# LED_I2C_Plug-Miller.net
KiCad netlist of a schematic drawn in EAGLE
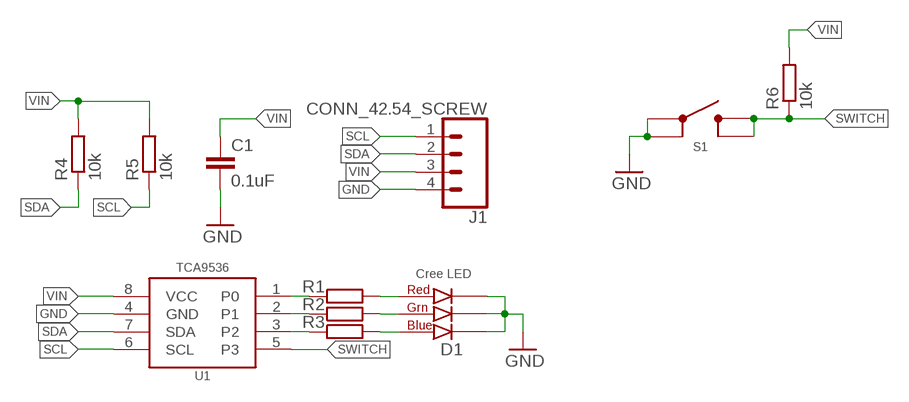
[diagram p0: schematic, sheet 1]

(export (version "E")
  (design (tool "Eeschema 10.0.6"))
  (components
    (comp (ref "C1")
      (value "0.1uF")
      (footprint "eagle-import:C0603")
      (fields (field (name "MF") "Murata") (field (name "MPN") "GCM188R71E104KA57D"))
      (libsource (lib "eagle-import") (part "C-EUC06030.1UF"))
    )
    (comp (ref "D1")
      (value "CLX6F-FKC")
      (footprint "eagle-import:CLX6F-FKC")
      (libsource (lib "eagle-import") (part "CLX6F-FKC"))
    )
    (comp (ref "J1")
      (value "CONN_42.54_SCREW")
      (footprint "eagle-import:1X04_SCREW")
      (fields (field (name "MF") "On Shore") (field (name "MPN") "OSTVN04A150"))
      (libsource (lib "eagle-import") (part "CONN_42.54_SCREW"))
    )
    (comp (ref "R1")
      (value "R-EU_330R0603")
      (footprint "eagle-import:R0603")
      (fields
        (field (name "MF") "Yageo")
        (field (name "MPN") "RC0603FR-07330RL")
        (field (name "VALUE_PART") "330")
      )
      (libsource (lib "eagle-import") (part "R-EU_R0603330"))
    )
    (comp (ref "R2")
      (value "R-EU_330R0603")
      (footprint "eagle-import:R0603")
      (fields
        (field (name "MF") "Yageo")
        (field (name "MPN") "RC0603FR-07330RL")
        (field (name "VALUE_PART") "330")
      )
      (libsource (lib "eagle-import") (part "R-EU_R0603330"))
    )
    (comp (ref "R3")
      (value "R-EU_330R0603")
      (footprint "eagle-import:R0603")
      (fields
        (field (name "MF") "Yageo")
        (field (name "MPN") "RC0603FR-07330RL")
        (field (name "VALUE_PART") "330")
      )
      (libsource (lib "eagle-import") (part "R-EU_R0603330"))
    )
    (comp (ref "R4")
      (value "10k")
      (footprint "eagle-import:R0603")
      (fields (field (name "MF") "Yageo") (field (name "MPN") "RC0603FR-0710KL"))
      (libsource (lib "eagle-import") (part "R-EU_R060310K"))
    )
    (comp (ref "R5")
      (value "10k")
      (footprint "eagle-import:R0603")
      (fields (field (name "MF") "Yageo") (field (name "MPN") "RC0603FR-0710KL"))
      (libsource (lib "eagle-import") (part "R-EU_R060310K"))
    )
    (comp (ref "R6")
      (value "10k")
      (footprint "eagle-import:R0603")
      (fields (field (name "MF") "Yageo") (field (name "MPN") "RC0603FR-0710KL"))
      (libsource (lib "eagle-import") (part "R-EU_R060310K"))
    )
    (comp (ref "S1")
      (value "BUTTON4.2X3.2")
      (footprint "eagle-import:SWITCH_4.2X3.2")
      (fields (field (name "MF") "C&K") (field (name "MPN") "PTS810 SJG 250 SMTR LFS"))
      (libsource (lib "eagle-import") (part "BUTTON4.2X3.2"))
    )
    (comp (ref "U1")
      (value "PCA9536VSSOP")
      (footprint "eagle-import:DGK_S-PDSO-G8")
      (fields (field (name "MF") "TI") (field (name "MPN") "PCA9536DGKR"))
      (libsource (lib "eagle-import") (part "PCA9536VSSOP"))
    )
  )
  (nets
    (net (code "1") (name "GND") (class "Default")
      (node (ref "C1") (pin "2") (pinfunction "2_2") (pintype "passive"))
      (node (ref "D1") (pin "P$1") (pinfunction "4_P$1") (pintype "bidirectional"))
      (node (ref "D1") (pin "P$2") (pinfunction "5_P$2") (pintype "bidirectional"))
      (node (ref "D1") (pin "P$3") (pinfunction "6_P$3") (pintype "bidirectional"))
      (node (ref "J1") (pin "4") (pinfunction "4_4") (pintype "passive"))
      (node (ref "S1") (pin "1") (pinfunction "1_1") (pintype "bidirectional"))
      (node (ref "S1") (pin "2") (pinfunction "2_2") (pintype "bidirectional"))
      (node (ref "U1") (pin "4") (pinfunction "GND_4") (pintype "power_in"))
    )
    (net (code "2") (name "Net-(D1-1)") (class "Default")
      (node (ref "D1") (pin "P$4") (pinfunction "1_P$4") (pintype "bidirectional"))
      (node (ref "R1") (pin "2") (pinfunction "2_2") (pintype "passive"))
    )
    (net (code "3") (name "Net-(D1-2)") (class "Default")
      (node (ref "D1") (pin "P$5") (pinfunction "2_P$5") (pintype "bidirectional"))
      (node (ref "R2") (pin "2") (pinfunction "2_2") (pintype "passive"))
    )
    (net (code "4") (name "Net-(D1-3)") (class "Default")
      (node (ref "D1") (pin "P$6") (pinfunction "3_P$6") (pintype "bidirectional"))
      (node (ref "R3") (pin "2") (pinfunction "2_2") (pintype "passive"))
    )
    (net (code "5") (name "Net-(U1-P0)") (class "Default")
      (node (ref "R1") (pin "1") (pinfunction "1_1") (pintype "passive"))
      (node (ref "U1") (pin "1") (pinfunction "P0_1") (pintype "bidirectional"))
    )
    (net (code "6") (name "Net-(U1-P1)") (class "Default")
      (node (ref "R2") (pin "1") (pinfunction "1_1") (pintype "passive"))
      (node (ref "U1") (pin "2") (pinfunction "P1_2") (pintype "bidirectional"))
    )
    (net (code "7") (name "Net-(U1-P2)") (class "Default")
      (node (ref "R3") (pin "1") (pinfunction "1_1") (pintype "passive"))
      (node (ref "U1") (pin "3") (pinfunction "P2_3") (pintype "bidirectional"))
    )
    (net (code "8") (name "SCL") (class "Default")
      (node (ref "J1") (pin "1") (pinfunction "1_1") (pintype "passive"))
      (node (ref "R5") (pin "1") (pinfunction "1_1") (pintype "passive"))
      (node (ref "U1") (pin "6") (pinfunction "SCL_6") (pintype "input"))
    )
    (net (code "9") (name "SDA") (class "Default")
      (node (ref "J1") (pin "2") (pinfunction "2_2") (pintype "passive"))
      (node (ref "R4") (pin "1") (pinfunction "1_1") (pintype "passive"))
      (node (ref "U1") (pin "7") (pinfunction "SDA_7") (pintype "bidirectional"))
    )
    (net (code "10") (name "SWITCH") (class "Default")
      (node (ref "R6") (pin "1") (pinfunction "1_1") (pintype "passive"))
      (node (ref "S1") (pin "3") (pinfunction "4_3") (pintype "bidirectional"))
      (node (ref "S1") (pin "4") (pinfunction "3_4") (pintype "bidirectional"))
      (node (ref "U1") (pin "5") (pinfunction "P3_5") (pintype "bidirectional"))
    )
    (net (code "11") (name "VIN") (class "Default")
      (node (ref "C1") (pin "1") (pinfunction "1_1") (pintype "passive"))
      (node (ref "J1") (pin "3") (pinfunction "3_3") (pintype "passive"))
      (node (ref "R4") (pin "2") (pinfunction "2_2") (pintype "passive"))
      (node (ref "R5") (pin "2") (pinfunction "2_2") (pintype "passive"))
      (node (ref "R6") (pin "2") (pinfunction "2_2") (pintype "passive"))
      (node (ref "U1") (pin "8") (pinfunction "VCC_8") (pintype "power_in"))
    )
  )
)
